# interface.net
KiCad netlist of a schematic drawn in EAGLE
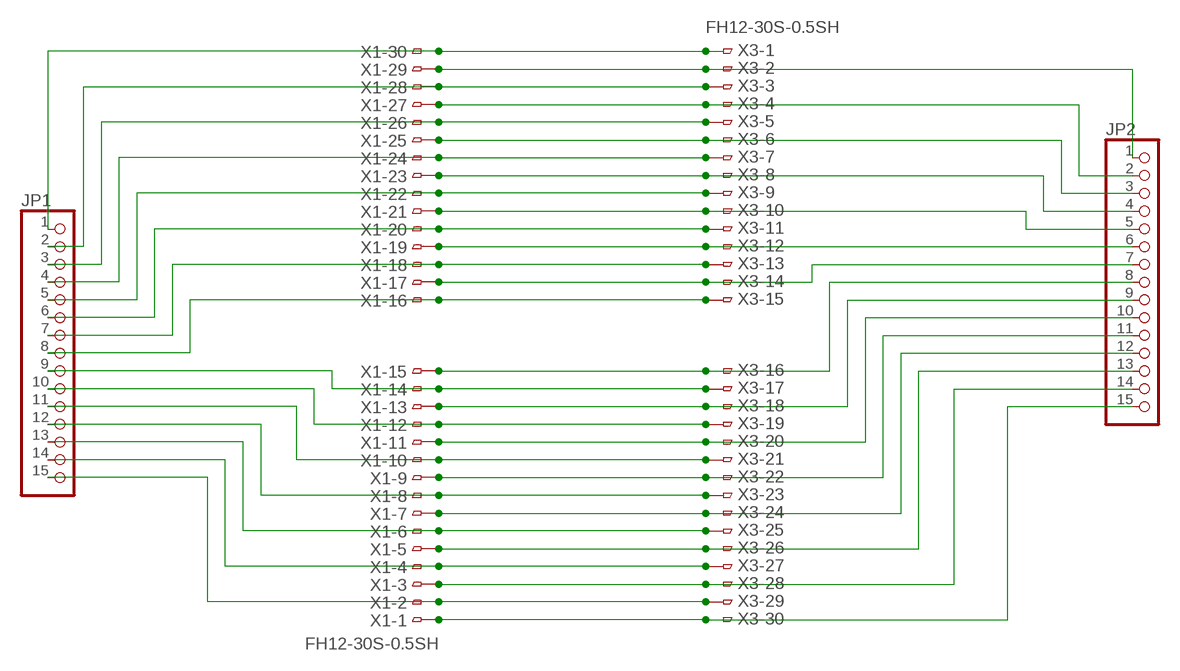
[diagram p0: schematic, sheet 1]

(export (version "E")
  (design (tool "Eeschema 10.0.6"))
  (components
    (comp (ref "JP1")
      (value "PINHD-1X15")
      (footprint "eagle-import:1X15")
      (libsource (lib "eagle-import") (part "PINHD-1X15"))
    )
    (comp (ref "JP2")
      (value "PINHD-1X15")
      (footprint "eagle-import:1X15")
      (libsource (lib "eagle-import") (part "PINHD-1X15"))
    )
    (comp (ref "X1")
      (value "FH12-30S-0.5SH")
      (footprint "eagle-import:FH12-30S-0.5SH")
      (fields (field (name "MPN") "FH12-30S-0.5SH(55)"))
      (libsource (lib "eagle-import") (part "FH12-30S-0.5SH"))
    )
    (comp (ref "X3")
      (value "FH12-30S-0.5SH")
      (footprint "eagle-import:FH12-30S-0.5SH")
      (fields (field (name "MPN") "FH12-30S-0.5SH(55)"))
      (libsource (lib "eagle-import") (part "FH12-30S-0.5SH"))
    )
  )
  (nets
    (net (code "1") (name "Net-(X1AA-1)") (class "Default")
      (node (ref "JP1") (pin "13") (pinfunction "13_13") (pintype "passive"))
      (node (ref "X1") (pin "6") (pinfunction "1_6") (pintype "passive"))
      (node (ref "X3") (pin "25") (pinfunction "1_25") (pintype "passive"))
    )
    (net (code "2") (name "Net-(X1AB-1)") (class "Default")
      (node (ref "JP2") (pin "12") (pinfunction "12_12") (pintype "passive"))
      (node (ref "X1") (pin "7") (pinfunction "1_7") (pintype "passive"))
      (node (ref "X3") (pin "24") (pinfunction "1_24") (pintype "passive"))
    )
    (net (code "3") (name "Net-(X1AC-1)") (class "Default")
      (node (ref "JP1") (pin "12") (pinfunction "12_12") (pintype "passive"))
      (node (ref "X1") (pin "8") (pinfunction "1_8") (pintype "passive"))
      (node (ref "X3") (pin "23") (pinfunction "1_23") (pintype "passive"))
    )
    (net (code "4") (name "Net-(X1AD-1)") (class "Default")
      (node (ref "JP2") (pin "11") (pinfunction "11_11") (pintype "passive"))
      (node (ref "X1") (pin "9") (pinfunction "1_9") (pintype "passive"))
      (node (ref "X3") (pin "22") (pinfunction "1_22") (pintype "passive"))
    )
    (net (code "5") (name "Net-(X1B-1)") (class "Default")
      (node (ref "JP1") (pin "11") (pinfunction "11_11") (pintype "passive"))
      (node (ref "X1") (pin "10") (pinfunction "1_10") (pintype "passive"))
      (node (ref "X3") (pin "21") (pinfunction "1_21") (pintype "passive"))
    )
    (net (code "6") (name "Net-(X1C-1)") (class "Default")
      (node (ref "JP2") (pin "10") (pinfunction "10_10") (pintype "passive"))
      (node (ref "X1") (pin "11") (pinfunction "1_11") (pintype "passive"))
      (node (ref "X3") (pin "20") (pinfunction "1_20") (pintype "passive"))
    )
    (net (code "7") (name "Net-(X1D-1)") (class "Default")
      (node (ref "JP1") (pin "10") (pinfunction "10_10") (pintype "passive"))
      (node (ref "X1") (pin "12") (pinfunction "1_12") (pintype "passive"))
      (node (ref "X3") (pin "19") (pinfunction "1_19") (pintype "passive"))
    )
    (net (code "8") (name "Net-(X1E-1)") (class "Default")
      (node (ref "JP2") (pin "9") (pinfunction "9_9") (pintype "passive"))
      (node (ref "X1") (pin "13") (pinfunction "1_13") (pintype "passive"))
      (node (ref "X3") (pin "18") (pinfunction "1_18") (pintype "passive"))
    )
    (net (code "9") (name "Net-(X1F-1)") (class "Default")
      (node (ref "JP1") (pin "9") (pinfunction "9_9") (pintype "passive"))
      (node (ref "X1") (pin "14") (pinfunction "1_14") (pintype "passive"))
      (node (ref "X3") (pin "17") (pinfunction "1_17") (pintype "passive"))
    )
    (net (code "10") (name "Net-(X1G-1)") (class "Default")
      (node (ref "JP2") (pin "8") (pinfunction "8_8") (pintype "passive"))
      (node (ref "X1") (pin "15") (pinfunction "1_15") (pintype "passive"))
      (node (ref "X3") (pin "16") (pinfunction "1_16") (pintype "passive"))
    )
    (net (code "11") (name "Net-(X1H-1)") (class "Default")
      (node (ref "JP1") (pin "8") (pinfunction "8_8") (pintype "passive"))
      (node (ref "X1") (pin "16") (pinfunction "1_16") (pintype "passive"))
      (node (ref "X3") (pin "15") (pinfunction "1_15") (pintype "passive"))
    )
    (net (code "12") (name "Net-(X1I-1)") (class "Default")
      (node (ref "JP2") (pin "7") (pinfunction "7_7") (pintype "passive"))
      (node (ref "X1") (pin "17") (pinfunction "1_17") (pintype "passive"))
      (node (ref "X3") (pin "14") (pinfunction "1_14") (pintype "passive"))
    )
    (net (code "13") (name "Net-(X1J-1)") (class "Default")
      (node (ref "JP1") (pin "7") (pinfunction "7_7") (pintype "passive"))
      (node (ref "X1") (pin "18") (pinfunction "1_18") (pintype "passive"))
      (node (ref "X3") (pin "13") (pinfunction "1_13") (pintype "passive"))
    )
    (net (code "14") (name "Net-(X1K-1)") (class "Default")
      (node (ref "JP2") (pin "6") (pinfunction "6_6") (pintype "passive"))
      (node (ref "X1") (pin "19") (pinfunction "1_19") (pintype "passive"))
      (node (ref "X3") (pin "12") (pinfunction "1_12") (pintype "passive"))
    )
    (net (code "15") (name "Net-(X1L-1)") (class "Default")
      (node (ref "JP1") (pin "15") (pinfunction "15_15") (pintype "passive"))
      (node (ref "X1") (pin "2") (pinfunction "1_2") (pintype "passive"))
      (node (ref "X3") (pin "29") (pinfunction "1_29") (pintype "passive"))
    )
    (net (code "16") (name "Net-(X1M-1)") (class "Default")
      (node (ref "JP1") (pin "6") (pinfunction "6_6") (pintype "passive"))
      (node (ref "X1") (pin "20") (pinfunction "1_20") (pintype "passive"))
      (node (ref "X3") (pin "11") (pinfunction "1_11") (pintype "passive"))
    )
    (net (code "17") (name "Net-(X1N-1)") (class "Default")
      (node (ref "JP2") (pin "5") (pinfunction "5_5") (pintype "passive"))
      (node (ref "X1") (pin "21") (pinfunction "1_21") (pintype "passive"))
      (node (ref "X3") (pin "10") (pinfunction "1_10") (pintype "passive"))
    )
    (net (code "18") (name "Net-(X1O-1)") (class "Default")
      (node (ref "JP1") (pin "5") (pinfunction "5_5") (pintype "passive"))
      (node (ref "X1") (pin "22") (pinfunction "1_22") (pintype "passive"))
      (node (ref "X3") (pin "9") (pinfunction "1_9") (pintype "passive"))
    )
    (net (code "19") (name "Net-(X1P-1)") (class "Default")
      (node (ref "JP2") (pin "4") (pinfunction "4_4") (pintype "passive"))
      (node (ref "X1") (pin "23") (pinfunction "1_23") (pintype "passive"))
      (node (ref "X3") (pin "8") (pinfunction "1_8") (pintype "passive"))
    )
    (net (code "20") (name "Net-(X1Q-1)") (class "Default")
      (node (ref "JP1") (pin "4") (pinfunction "4_4") (pintype "passive"))
      (node (ref "X1") (pin "24") (pinfunction "1_24") (pintype "passive"))
      (node (ref "X3") (pin "7") (pinfunction "1_7") (pintype "passive"))
    )
    (net (code "21") (name "Net-(X1R-1)") (class "Default")
      (node (ref "JP2") (pin "3") (pinfunction "3_3") (pintype "passive"))
      (node (ref "X1") (pin "25") (pinfunction "1_25") (pintype "passive"))
      (node (ref "X3") (pin "6") (pinfunction "1_6") (pintype "passive"))
    )
    (net (code "22") (name "Net-(X1S-1)") (class "Default")
      (node (ref "JP1") (pin "3") (pinfunction "3_3") (pintype "passive"))
      (node (ref "X1") (pin "26") (pinfunction "1_26") (pintype "passive"))
      (node (ref "X3") (pin "5") (pinfunction "1_5") (pintype "passive"))
    )
    (net (code "23") (name "Net-(X1T-1)") (class "Default")
      (node (ref "JP2") (pin "2") (pinfunction "2_2") (pintype "passive"))
      (node (ref "X1") (pin "27") (pinfunction "1_27") (pintype "passive"))
      (node (ref "X3") (pin "4") (pinfunction "1_4") (pintype "passive"))
    )
    (net (code "24") (name "Net-(X1U-1)") (class "Default")
      (node (ref "JP1") (pin "2") (pinfunction "2_2") (pintype "passive"))
      (node (ref "X1") (pin "28") (pinfunction "1_28") (pintype "passive"))
      (node (ref "X3") (pin "3") (pinfunction "1_3") (pintype "passive"))
    )
    (net (code "25") (name "Net-(X1V-1)") (class "Default")
      (node (ref "JP2") (pin "1") (pinfunction "1_1") (pintype "passive"))
      (node (ref "X1") (pin "29") (pinfunction "1_29") (pintype "passive"))
      (node (ref "X3") (pin "2") (pinfunction "1_2") (pintype "passive"))
    )
    (net (code "26") (name "Net-(X1W-1)") (class "Default")
      (node (ref "JP2") (pin "14") (pinfunction "14_14") (pintype "passive"))
      (node (ref "X1") (pin "3") (pinfunction "1_3") (pintype "passive"))
      (node (ref "X3") (pin "28") (pinfunction "1_28") (pintype "passive"))
    )
    (net (code "27") (name "Net-(X1X-1)") (class "Default")
      (node (ref "JP1") (pin "1") (pinfunction "1_1") (pintype "passive"))
      (node (ref "X1") (pin "30") (pinfunction "1_30") (pintype "passive"))
      (node (ref "X3") (pin "1") (pinfunction "1_1") (pintype "passive"))
    )
    (net (code "28") (name "Net-(X1Y-1)") (class "Default")
      (node (ref "JP1") (pin "14") (pinfunction "14_14") (pintype "passive"))
      (node (ref "X1") (pin "4") (pinfunction "1_4") (pintype "passive"))
      (node (ref "X3") (pin "27") (pinfunction "1_27") (pintype "passive"))
    )
    (net (code "29") (name "Net-(X1Z-1)") (class "Default")
      (node (ref "JP2") (pin "13") (pinfunction "13_13") (pintype "passive"))
      (node (ref "X1") (pin "5") (pinfunction "1_5") (pintype "passive"))
      (node (ref "X3") (pin "26") (pinfunction "1_26") (pintype "passive"))
    )
    (net (code "30") (name "Net-(X3X-1)") (class "Default")
      (node (ref "JP2") (pin "15") (pinfunction "15_15") (pintype "passive"))
      (node (ref "X1") (pin "1") (pinfunction "1_1") (pintype "passive"))
      (node (ref "X3") (pin "30") (pinfunction "1_30") (pintype "passive"))
    )
  )
)
